# Sheet1.net
KiCad netlist of a schematic drawn in Altium Designer
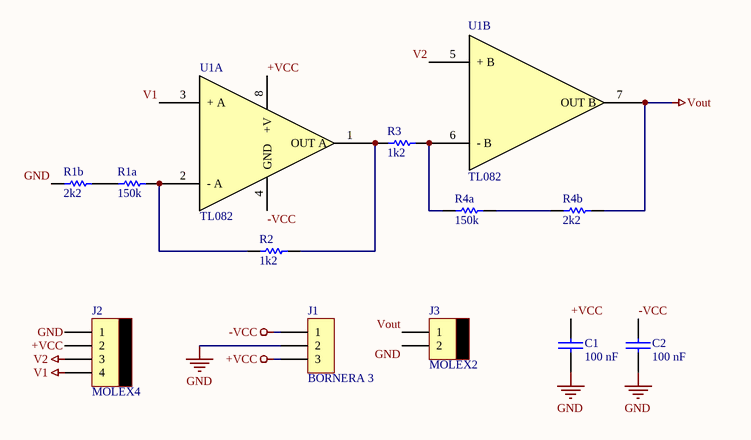
[diagram p0: Sheet1.SchDoc]

(export (version "E")
  (design (tool "Eeschema 10.0.6"))
  (components
    (comp (ref "C1") (value "100 nF") (footprint "CAP100") (libsource (lib "LIBEBAL") (part "CAP")))
    (comp (ref "C2") (value "100 nF") (footprint "CAP100") (libsource (lib "LIBEBAL") (part "CAP")))
    (comp (ref "J1")
      (value "BORNERA 3")
      (footprint "BORNERA3")
      (libsource (lib "LIBEBAL") (part "BORNERA 3"))
    )
    (comp (ref "J2") (value "MOLEX4") (footprint "MOLEX4") (libsource (lib "LIBEBAL") (part "MOLEX4")))
    (comp (ref "J3") (value "MOLEX2") (footprint "MOLEX2") (libsource (lib "LIBEBAL") (part "MOLEX2")))
    (comp (ref "R1a") (value "150k") (footprint "RES400") (libsource (lib "LIBEBAL") (part "RES")))
    (comp (ref "R1b") (value "2k2") (footprint "0805") (libsource (lib "LIBEBAL") (part "RES")))
    (comp (ref "R2") (value "1k2") (footprint "0805") (libsource (lib "LIBEBAL") (part "RES")))
    (comp (ref "R3") (value "1k2") (footprint "0805") (libsource (lib "LIBEBAL") (part "RES")))
    (comp (ref "R4a") (value "150k") (footprint "0805") (libsource (lib "LIBEBAL") (part "RES")))
    (comp (ref "R4b") (value "2k2") (footprint "0805") (libsource (lib "LIBEBAL") (part "RES")))
    (comp (ref "U1")
      (value "TL082")
      (footprint "DIP8")
      (description "Dual Audio Operational Amplifier")
      (libsource (lib "LIBEBAL") (part "LM833"))
    )
  )
  (nets
    (net (code "1") (name "+VCC") (class "Default")
      (node (ref "C1") (pin "1") (pinfunction "1_1") (pintype "passive"))
      (node (ref "J1") (pin "3") (pinfunction "3_3") (pintype "passive"))
      (node (ref "J2") (pin "2") (pinfunction "2_2") (pintype "passive"))
      (node (ref "U1") (pin "8") (pinfunction "+V_8") (pintype "passive"))
    )
    (net (code "2") (name "-VCC") (class "Default")
      (node (ref "C2") (pin "1") (pinfunction "1_1") (pintype "passive"))
      (node (ref "J1") (pin "1") (pinfunction "1_1") (pintype "passive"))
      (node (ref "U1") (pin "4") (pinfunction "GND_4") (pintype "passive"))
    )
    (net (code "3") (name "GND") (class "Default")
      (node (ref "C1") (pin "2") (pinfunction "2_2") (pintype "passive"))
      (node (ref "C2") (pin "2") (pinfunction "2_2") (pintype "passive"))
      (node (ref "J1") (pin "2") (pinfunction "2_2") (pintype "passive"))
      (node (ref "J2") (pin "1") (pinfunction "1_1") (pintype "passive"))
      (node (ref "J3") (pin "2") (pinfunction "2_2") (pintype "passive"))
      (node (ref "R1b") (pin "1") (pinfunction "1_1") (pintype "passive"))
    )
    (net (code "4") (name "Net-(R1a-Pad1)") (class "Default")
      (node (ref "R1a") (pin "1") (pinfunction "1_1") (pintype "passive"))
      (node (ref "R1b") (pin "2") (pinfunction "2_2") (pintype "passive"))
    )
    (net (code "5") (name "Net-(R4a-Pad2)") (class "Default")
      (node (ref "R4a") (pin "2") (pinfunction "2_2") (pintype "passive"))
      (node (ref "R4b") (pin "1") (pinfunction "1_1") (pintype "passive"))
    )
    (net (code "6") (name "Net-(U1A--_A)") (class "Default")
      (node (ref "R1a") (pin "2") (pinfunction "2_2") (pintype "passive"))
      (node (ref "R2") (pin "1") (pinfunction "1_1") (pintype "passive"))
      (node (ref "U1") (pin "2") (pinfunction "-_A_2") (pintype "passive"))
    )
    (net (code "7") (name "Net-(U1A-OUT_A)") (class "Default")
      (node (ref "R2") (pin "2") (pinfunction "2_2") (pintype "passive"))
      (node (ref "R3") (pin "1") (pinfunction "1_1") (pintype "passive"))
      (node (ref "U1") (pin "1") (pinfunction "OUT_A_1") (pintype "passive"))
    )
    (net (code "8") (name "Net-(U1B--_B)") (class "Default")
      (node (ref "R3") (pin "2") (pinfunction "2_2") (pintype "passive"))
      (node (ref "R4a") (pin "1") (pinfunction "1_1") (pintype "passive"))
      (node (ref "U1") (pin "6") (pinfunction "-_B_6") (pintype "passive"))
    )
    (net (code "9") (name "V1") (class "Default")
      (node (ref "J2") (pin "4") (pinfunction "4_4") (pintype "passive"))
      (node (ref "U1") (pin "3") (pinfunction "+_A_3") (pintype "passive"))
    )
    (net (code "10") (name "V2") (class "Default")
      (node (ref "J2") (pin "3") (pinfunction "3_3") (pintype "passive"))
      (node (ref "U1") (pin "5") (pinfunction "+_B_5") (pintype "passive"))
    )
    (net (code "11") (name "Vout") (class "Default")
      (node (ref "J3") (pin "1") (pinfunction "1_1") (pintype "passive"))
      (node (ref "R4b") (pin "2") (pinfunction "2_2") (pintype "passive"))
      (node (ref "U1") (pin "7") (pinfunction "OUT_B_7") (pintype "passive"))
    )
  )
)
